# stm32wb55vgy6-breakout.net
KiCad netlist of a schematic drawn in EAGLE
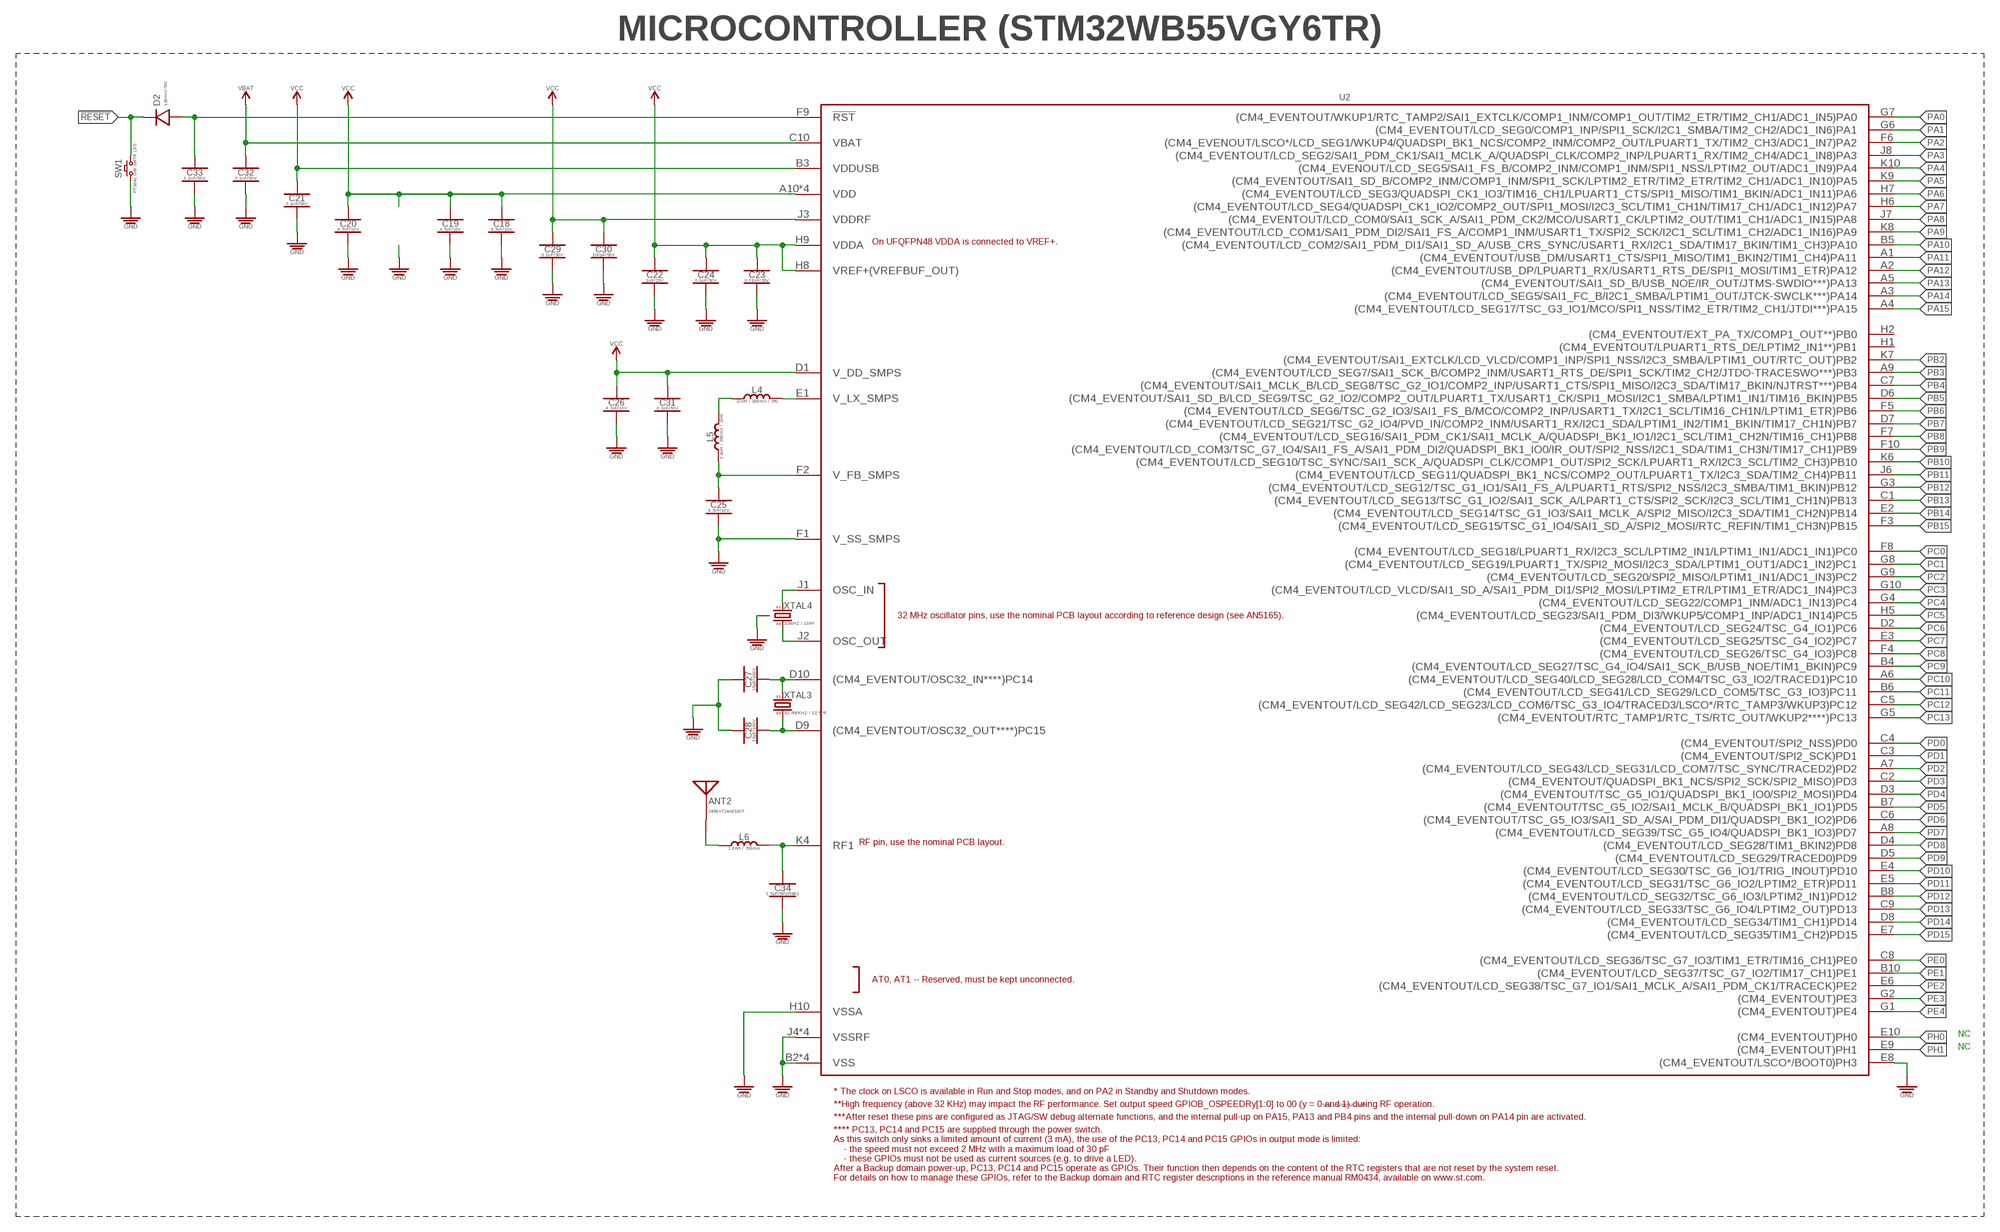
[diagram p0: schematic, sheet 1, part 1 of 2]
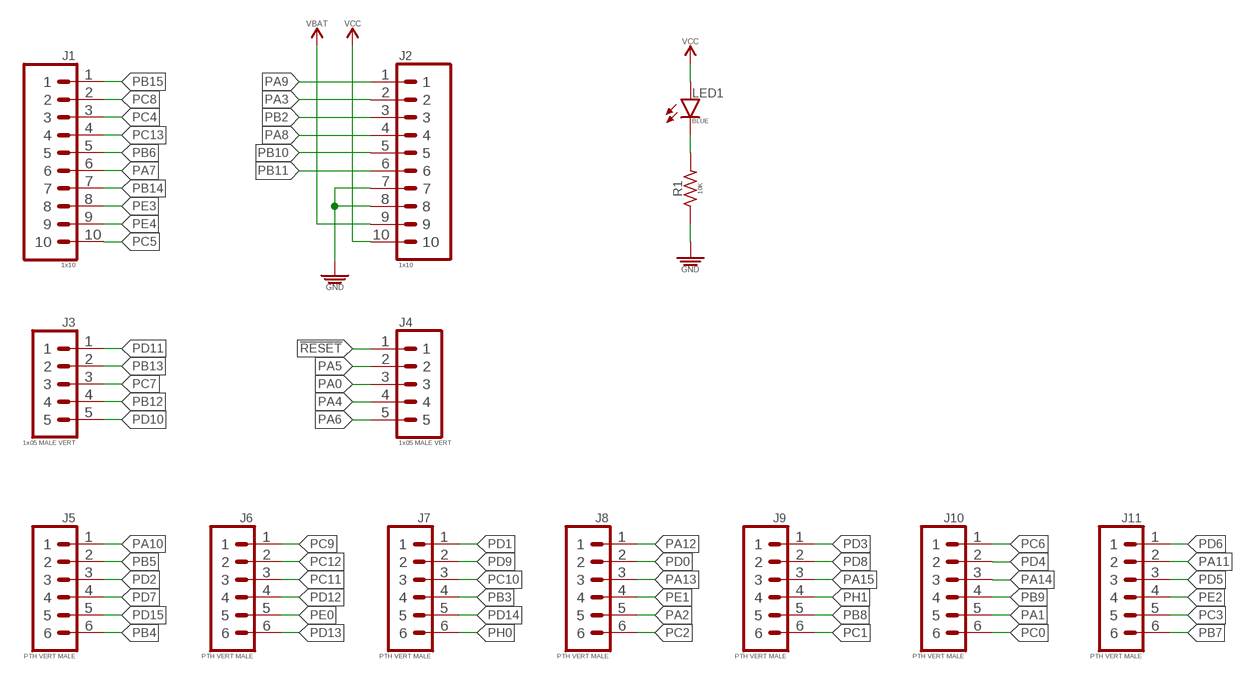
[diagram p1: schematic, sheet 1, part 2 of 2]

(export (version "E")
  (design (tool "Eeschema 10.0.6"))
  (components
    (comp (ref "ANT2")
      (value "2450AT14A0100T")
      (footprint "eagle-import:RESC1608X40N")
      (fields (field (name "MFR") "Johanson Technology Inc."))
      (libsource (lib "eagle-import") (part "2.4GHZ-1PIN"))
    )
    (comp (ref "C18")
      (value "4.7uF/10V")
      (footprint "eagle-import:CAPC1005X55_SMD-0402")
      (fields (field (name "MFR") "Samsung Electro-Mechanics") (field (name "MPN") "CL05A475MP5NRNC"))
      (libsource (lib "eagle-import") (part "4.7UF_CER_SMD-0402_10V-20%"))
    )
    (comp (ref "C19")
      (value "4.7uF/10V")
      (footprint "eagle-import:CAPC1005X55_SMD-0402")
      (fields (field (name "MFR") "Samsung Electro-Mechanics") (field (name "MPN") "CL05A475MP5NRNC"))
      (libsource (lib "eagle-import") (part "4.7UF_CER_SMD-0402_10V-20%"))
    )
    (comp (ref "C20")
      (value "4.7uF/10V")
      (footprint "eagle-import:CAPC1005X55_SMD-0402")
      (fields (field (name "MFR") "Samsung Electro-Mechanics") (field (name "MPN") "CL05A475MP5NRNC"))
      (libsource (lib "eagle-import") (part "4.7UF_CER_SMD-0402_10V-20%"))
    )
    (comp (ref "C21")
      (value "0.1uF/50V")
      (footprint "eagle-import:CAPC1005X55_SMD-0402")
      (fields (field (name "MFR") "TDK Corporation") (field (name "MPN") "C1005X7R1H104K050BE"))
      (libsource (lib "eagle-import") (part "0.1UF_SMD-0402_50V-10%"))
    )
    (comp (ref "C22")
      (value "1uF/25V")
      (footprint "eagle-import:CAPC1005X55_SMD-0402")
      (fields (field (name "MFR") "TDK Corporation") (field (name "MPN") "CGB2A1X5R1E105K033BC"))
      (libsource (lib "eagle-import") (part "1UF_CER_SMD-0402_25V-10%"))
    )
    (comp (ref "C23")
      (value "0.01uF/35V")
      (footprint "eagle-import:CAPC1005X55_SMD-0402")
      (fields (field (name "MFR") "TDK Corporation") (field (name "MPN") "CGA2B3X5R1V103K050BB"))
      (libsource (lib "eagle-import") (part "0.01UF_CER_SMD-0402_35V-10%"))
    )
    (comp (ref "C24")
      (value "0.1uF/50V")
      (footprint "eagle-import:CAPC1005X55_SMD-0402")
      (fields (field (name "MFR") "TDK Corporation") (field (name "MPN") "C1005X7R1H104K050BE"))
      (libsource (lib "eagle-import") (part "0.1UF_SMD-0402_50V-10%"))
    )
    (comp (ref "C25")
      (value "4.7uF/10V")
      (footprint "eagle-import:CAPC1005X55_SMD-0402")
      (fields (field (name "MFR") "Samsung Electro-Mechanics") (field (name "MPN") "CL05A475MP5NRNC"))
      (libsource (lib "eagle-import") (part "4.7UF_CER_SMD-0402_10V-20%"))
    )
    (comp (ref "C26")
      (value "4.7uF/10V")
      (footprint "eagle-import:CAPC1005X55_SMD-0402")
      (fields (field (name "MFR") "Samsung Electro-Mechanics") (field (name "MPN") "CL05A475MP5NRNC"))
      (libsource (lib "eagle-import") (part "4.7UF_CER_SMD-0402_10V-20%"))
    )
    (comp (ref "C27")
      (value "15pF/100V")
      (footprint "eagle-import:CAPC1005X55_SMD-0402")
      (fields (field (name "MFR") "Taiyo Yuden") (field (name "MPN") "HMK105CG150JV-F"))
      (libsource (lib "eagle-import") (part "15PF_SMD-0402_100V-10%"))
    )
    (comp (ref "C28")
      (value "15pF/100V")
      (footprint "eagle-import:CAPC1005X55_SMD-0402")
      (fields (field (name "MFR") "Taiyo Yuden") (field (name "MPN") "HMK105CG150JV-F"))
      (libsource (lib "eagle-import") (part "15PF_SMD-0402_100V-10%"))
    )
    (comp (ref "C29")
      (value "0.1uF/50V")
      (footprint "eagle-import:CAPC1005X55_SMD-0402")
      (fields (field (name "MFR") "TDK Corporation") (field (name "MPN") "C1005X7R1H104K050BE"))
      (libsource (lib "eagle-import") (part "0.1UF_SMD-0402_50V-10%"))
    )
    (comp (ref "C30")
      (value "100pF/50V")
      (footprint "eagle-import:CAPC1005X55_SMD-0402")
      (fields (field (name "MFR") "AVX Corporation") (field (name "MPN") "04025C101KAT2A"))
      (libsource (lib "eagle-import") (part "100PF_SMD-0402_50V-10%"))
    )
    (comp (ref "C31")
      (value "0.1uF/50V")
      (footprint "eagle-import:CAPC1005X55_SMD-0402")
      (fields (field (name "MFR") "TDK Corporation") (field (name "MPN") "C1005X7R1H104K050BE"))
      (libsource (lib "eagle-import") (part "0.1UF_SMD-0402_50V-10%"))
    )
    (comp (ref "C32")
      (value "0.1uF/50V")
      (footprint "eagle-import:CAPC1005X55_SMD-0402")
      (fields (field (name "MFR") "TDK Corporation") (field (name "MPN") "C1005X7R1H104K050BE"))
      (libsource (lib "eagle-import") (part "0.1UF_SMD-0402_50V-10%"))
    )
    (comp (ref "C33")
      (value "0.1uF/50V")
      (footprint "eagle-import:CAPC1005X55_SMD-0402")
      (fields (field (name "MFR") "TDK Corporation") (field (name "MPN") "C1005X7R1H104K050BE"))
      (libsource (lib "eagle-import") (part "0.1UF_SMD-0402_50V-10%"))
    )
    (comp (ref "C34")
      (value "1.5pF/50V/0402")
      (footprint "eagle-import:CAPC1005X55_SMD-0402")
      (fields (field (name "MFR") "Taiyo Yuden") (field (name "MPN") "UVK105CH1R5BW-F"))
      (libsource (lib "eagle-import") (part "1.5PF_CER_SMD-0402-100V-5%"))
    )
    (comp (ref "D2")
      (value "150mA/75V")
      (footprint "eagle-import:DFN100X60X55-2")
      (fields (field (name "MFR") "Comchip Technology") (field (name "MPN") "CDSQR4148-HF"))
      (libsource (lib "eagle-import") (part "GENERAL-PURPOSE_SMD-0402_GP_150MA-75V"))
    )
    (comp (ref "J1")
      (value "1x10")
      (footprint "eagle-import:HDRV10W64P254_1X10_2540X254X838B")
      (fields (field (name "MFR") "Sullins Connector Solutions") (field (name "MPN") "PEC10SAAN"))
      (libsource (lib "eagle-import") (part "1X10_PTH_VERT-MALE_2.54MM"))
    )
    (comp (ref "J2")
      (value "1x10")
      (footprint "eagle-import:HDRV10W64P254_1X10_2540X254X838B")
      (fields (field (name "MFR") "Sullins Connector Solutions") (field (name "MPN") "PEC10SAAN"))
      (libsource (lib "eagle-import") (part "1X10_PTH_VERT-MALE_2.54MM"))
    )
    (comp (ref "J3")
      (value "1x05 MALE VERT")
      (footprint "eagle-import:HDRV5W64P254_1X5_1270X254X838B")
      (fields (field (name "MFR") "Sullins Connector Solutions") (field (name "MPN") "PEC05SAAN"))
      (libsource (lib "eagle-import") (part "1X05_PTH_VERT_MALE_2.54MM"))
    )
    (comp (ref "J4")
      (value "1x05 MALE VERT")
      (footprint "eagle-import:HDRV5W64P254_1X5_1270X254X838B")
      (fields (field (name "MFR") "Sullins Connector Solutions") (field (name "MPN") "PEC05SAAN"))
      (libsource (lib "eagle-import") (part "1X05_PTH_VERT_MALE_2.54MM"))
    )
    (comp (ref "J5")
      (value "PTH VERT MALE")
      (footprint "eagle-import:HDRV6W64P254_1X6_1524X254X838B")
      (fields (field (name "MFR") "Sullins Connector Solutions") (field (name "MPN") "PEC06SAAN"))
      (libsource (lib "eagle-import") (part "1X06_PTH_VERT_MALE_2.54MM"))
    )
    (comp (ref "J6")
      (value "PTH VERT MALE")
      (footprint "eagle-import:HDRV6W64P254_1X6_1524X254X838B")
      (fields (field (name "MFR") "Sullins Connector Solutions") (field (name "MPN") "PEC06SAAN"))
      (libsource (lib "eagle-import") (part "1X06_PTH_VERT_MALE_2.54MM"))
    )
    (comp (ref "J7")
      (value "PTH VERT MALE")
      (footprint "eagle-import:HDRV6W64P254_1X6_1524X254X838B")
      (fields (field (name "MFR") "Sullins Connector Solutions") (field (name "MPN") "PEC06SAAN"))
      (libsource (lib "eagle-import") (part "1X06_PTH_VERT_MALE_2.54MM"))
    )
    (comp (ref "J8")
      (value "PTH VERT MALE")
      (footprint "eagle-import:HDRV6W64P254_1X6_1524X254X838B")
      (fields (field (name "MFR") "Sullins Connector Solutions") (field (name "MPN") "PEC06SAAN"))
      (libsource (lib "eagle-import") (part "1X06_PTH_VERT_MALE_2.54MM"))
    )
    (comp (ref "J9")
      (value "PTH VERT MALE")
      (footprint "eagle-import:HDRV6W64P254_1X6_1524X254X838B")
      (fields (field (name "MFR") "Sullins Connector Solutions") (field (name "MPN") "PEC06SAAN"))
      (libsource (lib "eagle-import") (part "1X06_PTH_VERT_MALE_2.54MM"))
    )
    (comp (ref "J10")
      (value "PTH VERT MALE")
      (footprint "eagle-import:HDRV6W64P254_1X6_1524X254X838B")
      (fields (field (name "MFR") "Sullins Connector Solutions") (field (name "MPN") "PEC06SAAN"))
      (libsource (lib "eagle-import") (part "1X06_PTH_VERT_MALE_2.54MM"))
    )
    (comp (ref "J11")
      (value "PTH VERT MALE")
      (footprint "eagle-import:HDRV6W64P254_1X6_1524X254X838B")
      (fields (field (name "MFR") "Sullins Connector Solutions") (field (name "MPN") "PEC06SAAN"))
      (libsource (lib "eagle-import") (part "1X06_PTH_VERT_MALE_2.54MM"))
    )
    (comp (ref "L4")
      (value "10nH / 200mA / 2%")
      (footprint "eagle-import:INDC1005X32N")
      (fields (field (name "MFR") "TE Connectivity Passive Product") (field (name "MPN") "36401E10NGTDF"))
      (libsource (lib "eagle-import") (part "10NH_SMD-0402_200MA-1.35OHM-2%"))
    )
    (comp (ref "L5")
      (value "2.2uH / 350mA / 20%")
      (footprint "eagle-import:INDC1005X32N")
      (fields (field (name "MFR") "TDK Corporation") (field (name "MPN") "MLZ1005M2R2WT000"))
      (libsource (lib "eagle-import") (part "2.2UH_SMD-0402_350MA-0.550OHM-20%"))
    )
    (comp (ref "L6")
      (value "1.8nH / 700mA")
      (footprint "eagle-import:INDC1005X32N")
      (fields (field (name "MFR") "Taiyo Yuden") (field (name "MPN") "HK10051N8S-T"))
      (libsource (lib "eagle-import") (part "1.8NH_SMD-0402_200MA-1.35OHM-2%"))
    )
    (comp (ref "LED1")
      (value "BLUE")
      (footprint "eagle-import:LEDC1005X40_LED-0402")
      (fields (field (name "MFR") "Bivar Inc.") (field (name "MPN") "SM0402BWC"))
      (libsource (lib "eagle-import") (part "LED_SMD-0402_DISCRETE_BLUE"))
    )
    (comp (ref "R1")
      (value "10K")
      (footprint "eagle-import:RESC1005X35_SMD-0402")
      (fields (field (name "MFR") "Yageo") (field (name "MPN") "RC0402JR-0710KP"))
      (libsource (lib "eagle-import") (part "10KΩ_SMD-0402_1/16W-5%"))
    )
    (comp (ref "SW1")
      (value "PTS841 GM SMTR LFS")
      (footprint "eagle-import:SW_MOMENTARY_SPST-NO_PTS841-GM-SMTR-LFS")
      (fields (field (name "MFR") "C&K"))
      (libsource (lib "eagle-import") (part "SWITCH_MOMENTARY_PTS841GMSMTRLFS"))
    )
    (comp (ref "U2")
      (value "STM32WB55VGY6TR")
      (footprint "eagle-import:BGA100N40P10X10_438X440X59N")
      (fields (field (name "MFR") "STMicroelectronics"))
      (libsource (lib "eagle-import") (part "STM32WB55VXYX-STM32WB55VGY6"))
    )
    (comp (ref "XTAL3")
      (value "32.768KHZ / 12.5PF")
      (footprint "eagle-import:OSCCC205X120X55N")
      (fields (field (name "MFR") "NDK America, Inc.") (field (name "MPN") "NX2012SA-32.768K-STD-MUB-1"))
      (libsource (lib "eagle-import") (part "CRYSTAL-2_NX2012SA_23K768_12.5PF"))
    )
    (comp (ref "XTAL4")
      (value "32MHZ / 10PF")
      (footprint "eagle-import:OSCCC200X160X59N")
      (fields (field (name "MFR") "Abracon LLC") (field (name "MPN") "ABM11-32.000MHZ-D2X-T3"))
      (libsource (lib "eagle-import") (part "CRYSTAL-4_ABM11_32MHZ_10PF"))
    )
  )
  (nets
    (net (code "1") (name "/~{RESET}") (class "Default")
      (node (ref "D2") (pin "K") (pinfunction "K_K") (pintype "passive"))
      (node (ref "J4") (pin "1") (pinfunction "1_1") (pintype "passive"))
      (node (ref "SW1") (pin "3") (pinfunction "2_3") (pintype "passive"))
      (node (ref "SW1") (pin "4") (pinfunction "2_4") (pintype "passive"))
    )
    (net (code "2") (name "GND") (class "Default")
      (node (ref "C18") (pin "2") (pinfunction "2_2") (pintype "passive"))
      (node (ref "C19") (pin "2") (pinfunction "2_2") (pintype "passive"))
      (node (ref "C20") (pin "2") (pinfunction "2_2") (pintype "passive"))
      (node (ref "C21") (pin "2") (pinfunction "2_2") (pintype "passive"))
      (node (ref "C22") (pin "2") (pinfunction "2_2") (pintype "passive"))
      (node (ref "C23") (pin "2") (pinfunction "2_2") (pintype "passive"))
      (node (ref "C24") (pin "2") (pinfunction "2_2") (pintype "passive"))
      (node (ref "C25") (pin "2") (pinfunction "2_2") (pintype "passive"))
      (node (ref "C26") (pin "2") (pinfunction "2_2") (pintype "passive"))
      (node (ref "C27") (pin "1") (pinfunction "1_1") (pintype "passive"))
      (node (ref "C28") (pin "1") (pinfunction "1_1") (pintype "passive"))
      (node (ref "C29") (pin "2") (pinfunction "2_2") (pintype "passive"))
      (node (ref "C30") (pin "2") (pinfunction "2_2") (pintype "passive"))
      (node (ref "C31") (pin "2") (pinfunction "2_2") (pintype "passive"))
      (node (ref "C32") (pin "2") (pinfunction "2_2") (pintype "passive"))
      (node (ref "C33") (pin "2") (pinfunction "2_2") (pintype "passive"))
      (node (ref "C34") (pin "2") (pinfunction "2_2") (pintype "passive"))
      (node (ref "J2") (pin "7") (pinfunction "7_7") (pintype "passive"))
      (node (ref "J2") (pin "8") (pinfunction "8_8") (pintype "passive"))
      (node (ref "R1") (pin "1") (pinfunction "1_1") (pintype "passive"))
      (node (ref "SW1") (pin "1") (pinfunction "1_1") (pintype "passive"))
      (node (ref "SW1") (pin "2") (pinfunction "1_2") (pintype "passive"))
      (node (ref "U2") (pin "B2") (pinfunction "VSS_B2") (pintype "power_in"))
      (node (ref "U2") (pin "B9") (pinfunction "VSS_B9") (pintype "power_in"))
      (node (ref "U2") (pin "E8") (pinfunction "(CM4_EVENTOUT/LSCO*/BOOT0)PH3_E8") (pintype "bidirectional"))
      (node (ref "U2") (pin "F1") (pinfunction "V_SS_SMPS_F1") (pintype "power_in"))
      (node (ref "U2") (pin "H10") (pinfunction "VSSA_H10") (pintype "power_in"))
      (node (ref "U2") (pin "J4") (pinfunction "VSSRF_J4") (pintype "power_in"))
      (node (ref "U2") (pin "J5") (pinfunction "VSS_J5") (pintype "power_in"))
      (node (ref "U2") (pin "J9") (pinfunction "VSS_J9") (pintype "power_in"))
      (node (ref "U2") (pin "K1") (pinfunction "VSSRF_K1") (pintype "power_in"))
      (node (ref "U2") (pin "K2") (pinfunction "VSSRF_K2") (pintype "power_in"))
      (node (ref "U2") (pin "K3") (pinfunction "VSSRF_K3") (pintype "power_in"))
      (node (ref "XTAL4") (pin "2") (pinfunction "GND_2") (pintype "passive"))
      (node (ref "XTAL4") (pin "4") (pinfunction "GND_4") (pintype "passive"))
    )
    (net (code "3") (name "Net-(ANT2-PadFEED)") (class "Default")
      (node (ref "ANT2") (pin "FEED") (pinfunction "FEED_FEED") (pintype "passive"))
      (node (ref "L6") (pin "1") (pinfunction "1_1") (pintype "passive"))
    )
    (net (code "4") (name "Net-(L4-Pad1)") (class "Default")
      (node (ref "L4") (pin "1") (pinfunction "1_1") (pintype "passive"))
      (node (ref "L5") (pin "2") (pinfunction "2_2") (pintype "passive"))
    )
    (net (code "5") (name "Net-(LED1-PadK)") (class "Default")
      (node (ref "LED1") (pin "K") (pinfunction "K_K") (pintype "passive"))
      (node (ref "R1") (pin "2") (pinfunction "2_2") (pintype "passive"))
    )
    (net (code "6") (name "Net-(U2-(CM4_EVENTOUT{slash}OSC32_IN****)PC14)") (class "Default")
      (node (ref "C27") (pin "2") (pinfunction "2_2") (pintype "passive"))
      (node (ref "U2") (pin "D10") (pinfunction "(CM4_EVENTOUT/OSC32_IN****)PC14_D10") (pintype "bidirectional"))
      (node (ref "XTAL3") (pin "X1") (pinfunction "X1_X1") (pintype "passive"))
    )
    (net (code "7") (name "Net-(U2-(CM4_EVENTOUT{slash}OSC32_OUT****)PC15)") (class "Default")
      (node (ref "C28") (pin "2") (pinfunction "2_2") (pintype "passive"))
      (node (ref "U2") (pin "D9") (pinfunction "(CM4_EVENTOUT/OSC32_OUT****)PC15_D9") (pintype "bidirectional"))
      (node (ref "XTAL3") (pin "X2") (pinfunction "X2_X2") (pintype "passive"))
    )
    (net (code "8") (name "Net-(U2-OSC_IN)") (class "Default")
      (node (ref "U2") (pin "J1") (pinfunction "OSC_IN_J1") (pintype "bidirectional"))
      (node (ref "XTAL4") (pin "1") (pinfunction "XTAL1_1") (pintype "passive"))
    )
    (net (code "9") (name "Net-(U2-OSC_OUT)") (class "Default")
      (node (ref "U2") (pin "J2") (pinfunction "OSC_OUT_J2") (pintype "bidirectional"))
      (node (ref "XTAL4") (pin "3") (pinfunction "XTAL2_3") (pintype "passive"))
    )
    (net (code "10") (name "Net-(U2-RF1)") (class "Default")
      (node (ref "C34") (pin "1") (pinfunction "1_1") (pintype "passive"))
      (node (ref "L6") (pin "2") (pinfunction "2_2") (pintype "passive"))
      (node (ref "U2") (pin "K4") (pinfunction "RF1_K4") (pintype "bidirectional"))
    )
    (net (code "11") (name "Net-(U2-V_FB_SMPS)") (class "Default")
      (node (ref "C25") (pin "1") (pinfunction "1_1") (pintype "passive"))
      (node (ref "L5") (pin "1") (pinfunction "1_1") (pintype "passive"))
      (node (ref "U2") (pin "F2") (pinfunction "V_FB_SMPS_F2") (pintype "power_in"))
    )
    (net (code "12") (name "Net-(U2-V_LX_SMPS)") (class "Default")
      (node (ref "L4") (pin "2") (pinfunction "2_2") (pintype "passive"))
      (node (ref "U2") (pin "E1") (pinfunction "V_LX_SMPS_E1") (pintype "power_in"))
    )
    (net (code "13") (name "Net-(U2-~{RST})") (class "Default")
      (node (ref "C33") (pin "1") (pinfunction "1_1") (pintype "passive"))
      (node (ref "D2") (pin "A") (pinfunction "A_A") (pintype "passive"))
      (node (ref "U2") (pin "F9") (pinfunction "~{RST}_F9") (pintype "bidirectional"))
    )
    (net (code "14") (name "PA0") (class "Default")
      (node (ref "J4") (pin "3") (pinfunction "3_3") (pintype "passive"))
      (node (ref "U2") (pin "G7") (pinfunction "(CM4_EVENTOUT/WKUP1/RTC_TAMP2/SAI1_EXTCLK/COMP1_INM/COMP1_OUT/TIM2_ETR/TIM2_CH1/ADC1_IN5)PA0_G7") (pintype "bidirectional"))
    )
    (net (code "15") (name "PA1") (class "Default")
      (node (ref "J10") (pin "5") (pinfunction "5_5") (pintype "passive"))
      (node (ref "U2") (pin "G6") (pinfunction "(CM4_EVENTOUT/LCD_SEG0/COMP1_INP/SPI1_SCK/I2C1_SMBA/TIM2_CH2/ADC1_IN6)PA1_G6") (pintype "bidirectional"))
    )
    (net (code "16") (name "PA2") (class "Default")
      (node (ref "J8") (pin "5") (pinfunction "5_5") (pintype "passive"))
      (node (ref "U2") (pin "F6") (pinfunction "(CM4_EVENOUT/LSCO*/LCD_SEG1/WKUP4/QUADSPI_BK1_NCS/COMP2_INM/COMP2_OUT/LPUART1_TX/TIM2_CH3/ADC1_IN7)PA2_F6") (pintype "bidirectional"))
    )
    (net (code "17") (name "PA3") (class "Default")
      (node (ref "J2") (pin "2") (pinfunction "2_2") (pintype "passive"))
      (node (ref "U2") (pin "J8") (pinfunction "(CM4_EVENTOUT/LCD_SEG2/SAI1_PDM_CK1/SAI1_MCLK_A/QUADSPI_CLK/COMP2_INP/LPUART1_RX/TIM2_CH4/ADC1_IN8)PA3_J8") (pintype "bidirectional"))
    )
    (net (code "18") (name "PA4") (class "Default")
      (node (ref "J4") (pin "4") (pinfunction "4_4") (pintype "passive"))
      (node (ref "U2") (pin "K10") (pinfunction "(CM4_EVENOUT/LCD_SEG5/SAI1_FS_B/COMP2_INM/COMP1_INM/SPI1_NSS/LPTIM2_OUT/ADC1_IN9)PA4_K10") (pintype "bidirectional"))
    )
    (net (code "19") (name "PA5") (class "Default")
      (node (ref "J4") (pin "2") (pinfunction "2_2") (pintype "passive"))
      (node (ref "U2") (pin "K9") (pinfunction "(CM4_EVENTOUT/SAI1_SD_B/COMP2_INM/COMP1_INM/SPI1_SCK/LPTIM2_ETR/TIM2_ETR/TIM2_CH1/ADC1_IN10)PA5_K9") (pintype "bidirectional"))
    )
    (net (code "20") (name "PA6") (class "Default")
      (node (ref "J4") (pin "5") (pinfunction "5_5") (pintype "passive"))
      (node (ref "U2") (pin "H7") (pinfunction "(CM4_EVENTOUT/LCD_SEG3/QUADSPI_CK1_IO3/TIM16_CH1/LPUART1_CTS/SPI1_MISO/TIM1_BKIN/ADC1_IN11)PA6_H7") (pintype "bidirectional"))
    )
    (net (code "21") (name "PA7") (class "Default")
      (node (ref "J1") (pin "6") (pinfunction "6_6") (pintype "passive"))
      (node (ref "U2") (pin "H6") (pinfunction "(CM4_EVENTOUT/LCD_SEG4/QUADSPI_CK1_IO2/COMP2_OUT/SPI1_MOSI/I2C3_SCL/TIM1_CH1N/TIM17_CH1/ADC1_IN12)PA7_H6") (pintype "bidirectional"))
    )
    (net (code "22") (name "PA8") (class "Default")
      (node (ref "J2") (pin "4") (pinfunction "4_4") (pintype "passive"))
      (node (ref "U2") (pin "J7") (pinfunction "(CM4_EVENTOUT/LCD_COM0/SAI1_SCK_A/SAI1_PDM_CK2/MCO/USART1_CK/LPTIM2_OUT/TIM1_CH1/ADC1_IN15)PA8_J7") (pintype "bidirectional"))
    )
    (net (code "23") (name "PA9") (class "Default")
      (node (ref "J2") (pin "1") (pinfunction "1_1") (pintype "passive"))
      (node (ref "U2") (pin "K8") (pinfunction "(CM4_EVENTOUT/LCD_COM1/SAI1_PDM_DI2/SAI1_FS_A/COMP1_INM/USART1_TX/SPI2_SCK/I2C1_SCL/TIM1_CH2/ADC1_IN16)PA9_K8") (pintype "bidirectional"))
    )
    (net (code "24") (name "PA10") (class "Default")
      (node (ref "J5") (pin "1") (pinfunction "1_1") (pintype "passive"))
      (node (ref "U2") (pin "B5") (pinfunction "(CM4_EVENTOUT/LCD_COM2/SAI1_PDM_DI1/SAI1_SD_A/USB_CRS_SYNC/USART1_RX/I2C1_SDA/TIM17_BKIN/TIM1_CH3)PA10_B5") (pintype "bidirectional"))
    )
    (net (code "25") (name "PA11") (class "Default")
      (node (ref "J11") (pin "2") (pinfunction "2_2") (pintype "passive"))
      (node (ref "U2") (pin "A1") (pinfunction "(CM4_EVENTOUT/USB_DM/USART1_CTS/SPI1_MISO/TIM1_BKIN2/TIM1_CH4)PA11_A1") (pintype "bidirectional"))
    )
    (net (code "26") (name "PA12") (class "Default")
      (node (ref "J8") (pin "1") (pinfunction "1_1") (pintype "passive"))
      (node (ref "U2") (pin "A2") (pinfunction "(CM4_EVENTOUT/USB_DP/LPUART1_RX/USART1_RTS_DE/SPI1_MOSI/TIM1_ETR)PA12_A2") (pintype "bidirectional"))
    )
    (net (code "27") (name "PA13") (class "Default")
      (node (ref "J8") (pin "3") (pinfunction "3_3") (pintype "passive"))
      (node (ref "U2") (pin "A5") (pinfunction "(CM4_EVENTOUT/SAI1_SD_B/USB_NOE/IR_OUT/JTMS-SWDIO***)PA13_A5") (pintype "bidirectional"))
    )
    (net (code "28") (name "PA14") (class "Default")
      (node (ref "J10") (pin "3") (pinfunction "3_3") (pintype "passive"))
      (node (ref "U2") (pin "A3") (pinfunction "(CM4_EVENTOUT/LCD_SEG5/SAI1_FC_B/I2C1_SMBA/LPTIM1_OUT/JTCK-SWCLK***)PA14_A3") (pintype "bidirectional"))
    )
    (net (code "29") (name "PA15") (class "Default")
      (node (ref "J9") (pin "3") (pinfunction "3_3") (pintype "passive"))
      (node (ref "U2") (pin "A4") (pinfunction "(CM4_EVENTOUT/LCD_SEG17/TSC_G3_IO1/MCO/SPI1_NSS/TIM2_ETR/TIM2_CH1/JTDI***)PA15_A4") (pintype "bidirectional"))
    )
    (net (code "30") (name "PB2") (class "Default")
      (node (ref "J2") (pin "3") (pinfunction "3_3") (pintype "passive"))
      (node (ref "U2") (pin "K7") (pinfunction "(CM4_EVENTOUT/SAI1_EXTCLK/LCD_VLCD/COMP1_INP/SPI1_NSS/I2C3_SMBA/LPTIM1_OUT/RTC_OUT)PB2_K7") (pintype "bidirectional"))
    )
    (net (code "31") (name "PB3") (class "Default")
      (node (ref "J7") (pin "4") (pinfunction "4_4") (pintype "passive"))
      (node (ref "U2") (pin "A9") (pinfunction "(CM4_EVENTOUT/LCD_SEG7/SAI1_SCK_B/COMP2_INM/USART1_RTS_DE/SPI1_SCK/TIM2_CH2/JTDO-TRACESWO***)PB3_A9") (pintype "bidirectional"))
    )
    (net (code "32") (name "PB4") (class "Default")
      (node (ref "J5") (pin "6") (pinfunction "6_6") (pintype "passive"))
      (node (ref "U2") (pin "C7") (pinfunction "(CM4_EVENTOUT/SAI1_MCLK_B/LCD_SEG8/TSC_G2_IO1/COMP2_INP/USART1_CTS/SPI1_MISO/I2C3_SDA/TIM17_BKIN/NJTRST***)PB4_C7") (pintype "bidirectional"))
    )
    (net (code "33") (name "PB5") (class "Default")
      (node (ref "J5") (pin "2") (pinfunction "2_2") (pintype "passive"))
      (node (ref "U2") (pin "D6") (pinfunction "(CM4_EVENTOUT/SAI1_SD_B/LCD_SEG9/TSC_G2_IO2/COMP2_OUT/LPUART1_TX/USART1_CK/SPI1_MOSI/I2C1_SMBA/LPTIM1_IN1/TIM16_BKIN)PB5_D6") (pintype "bidirectional"))
    )
    (net (code "34") (name "PB6") (class "Default")
      (node (ref "J1") (pin "5") (pinfunction "5_5") (pintype "passive"))
      (node (ref "U2") (pin "F5") (pinfunction "(CM4_EVENTOUT/LCD_SEG6/TSC_G2_IO3/SAI1_FS_B/MCO/COMP2_INP/USART1_TX/I2C1_SCL/TIM16_CH1N/LPTIM1_ETR)PB6_F5") (pintype "bidirectional"))
    )
    (net (code "35") (name "PB7") (class "Default")
      (node (ref "J11") (pin "6") (pinfunction "6_6") (pintype "passive"))
      (node (ref "U2") (pin "D7") (pinfunction "(CM4_EVENTOUT/LCD_SEG21/TSC_G2_IO4/PVD_IN/COMP2_INM/USART1_RX/I2C1_SDA/LPTIM1_IN2/TIM1_BKIN/TIM17_CH1N)PB7_D7") (pintype "bidirectional"))
    )
    (net (code "36") (name "PB8") (class "Default")
      (node (ref "J9") (pin "5") (pinfunction "5_5") (pintype "passive"))
      (node (ref "U2") (pin "F7") (pinfunction "(CM4_EVENTOUT/LCD_SEG16/SAI1_PDM_CK1/SAI1_MCLK_A/QUADSPI_BK1_IO1/I2C1_SCL/TIM1_CH2N/TIM16_CH1)PB8_F7") (pintype "bidirectional"))
    )
    (net (code "37") (name "PB9") (class "Default")
      (node (ref "J10") (pin "4") (pinfunction "4_4") (pintype "passive"))
      (node (ref "U2") (pin "F10") (pinfunction "(CM4_EVENTOUT/LCD_COM3/TSC_G7_IO4/SAI1_FS_A/SAI1_PDM_DI2/QUADSPI_BK1_IO0/IR_OUT/SPI2_NSS/I2C1_SDA/TIM1_CH3N/TIM17_CH1)PB9_F10") (pintype "bidirectional"))
    )
    (net (code "38") (name "PB10") (class "Default")
      (node (ref "J2") (pin "5") (pinfunction "5_5") (pintype "passive"))
      (node (ref "U2") (pin "K6") (pinfunction "(CM4_EVENTOUT/LCD_SEG10/TSC_SYNC/SAI1_SCK_A/QUADSPI_CLK/COMP1_OUT/SPI2_SCK/LPUART1_RX/I2C3_SCL/TIM2_CH3)PB10_K6") (pintype "bidirectional"))
    )
    (net (code "39") (name "PB11") (class "Default")
      (node (ref "J2") (pin "6") (pinfunction "6_6") (pintype "passive"))
      (node (ref "U2") (pin "J6") (pinfunction "(CM4_EVENTOUT/LCD_SEG11/QUADSPI_BK1_NCS/COMP2_OUT/LPUART1_TX/I2C3_SDA/TIM2_CH4)PB11_J6") (pintype "bidirectional"))
    )
    (net (code "40") (name "PB12") (class "Default")
      (node (ref "J3") (pin "4") (pinfunction "4_4") (pintype "passive"))
      (node (ref "U2") (pin "G3") (pinfunction "(CM4_EVENTOUT/LCD_SEG12/TSC_G1_IO1/SAI1_FS_A/LPUART1_RTS/SPI2_NSS/I2C3_SMBA/TIM1_BKIN)PB12_G3") (pintype "bidirectional"))
    )
    (net (code "41") (name "PB13") (class "Default")
      (node (ref "J3") (pin "2") (pinfunction "2_2") (pintype "passive"))
      (node (ref "U2") (pin "C1") (pinfunction "(CM4_EVENTOUT/LCD_SEG13/TSC_G1_IO2/SAI1_SCK_A/LPART1_CTS/SPI2_SCK/I2C3_SCL/TIM1_CH1N)PB13_C1") (pintype "bidirectional"))
    )
    (net (code "42") (name "PB14") (class "Default")
      (node (ref "J1") (pin "7") (pinfunction "7_7") (pintype "passive"))
      (node (ref "U2") (pin "E2") (pinfunction "(CM4_EVENTOUT/LCD_SEG14/TSC_G1_IO3/SAI1_MCLK_A/SPI2_MISO/I2C3_SDA/TIM1_CH2N)PB14_E2") (pintype "bidirectional"))
    )
    (net (code "43") (name "PB15") (class "Default")
      (node (ref "J1") (pin "1") (pinfunction "1_1") (pintype "passive"))
      (node (ref "U2") (pin "F3") (pinfunction "(CM4_EVENTOUT/LCD_SEG15/TSC_G1_IO4/SAI1_SD_A/SPI2_MOSI/RTC_REFIN/TIM1_CH3N)PB15_F3") (pintype "bidirectional"))
    )
    (net (code "44") (name "PC0") (class "Default")
      (node (ref "J10") (pin "6") (pinfunction "6_6") (pintype "passive"))
      (node (ref "U2") (pin "F8") (pinfunction "(CM4_EVENTOUT/LCD_SEG18/LPUART1_RX/I2C3_SCL/LPTIM2_IN1/LPTIM1_IN1/ADC1_IN1)PC0_F8") (pintype "bidirectional"))
    )
    (net (code "45") (name "PC1") (class "Default")
      (node (ref "J9") (pin "6") (pinfunction "6_6") (pintype "passive"))
      (node (ref "U2") (pin "G8") (pinfunction "(CM4_EVENTOUT/LCD_SEG19/LPUART1_TX/SPI2_MOSI/I2C3_SDA/LPTIM1_OUT1/ADC1_IN2)PC1_G8") (pintype "bidirectional"))
    )
    (net (code "46") (name "PC2") (class "Default")
      (node (ref "J8") (pin "6") (pinfunction "6_6") (pintype "passive"))
      (node (ref "U2") (pin "G9") (pinfunction "(CM4_EVENTOUT/LCD_SEG20/SPI2_MISO/LPTIM1_IN1/ADC1_IN3)PC2_G9") (pintype "bidirectional"))
    )
    (net (code "47") (name "PC3") (class "Default")
      (node (ref "J11") (pin "5") (pinfunction "5_5") (pintype "passive"))
      (node (ref "U2") (pin "G10") (pinfunction "(CM4_EVENTOUT/LCD_VLCD/SAI1_SD_A/SAI1_PDM_DI1/SPI2_MOSI/LPTIM2_ETR/LPTIM1_ETR/ADC1_IN4)PC3_G10") (pintype "bidirectional"))
    )
    (net (code "48") (name "PC4") (class "Default")
      (node (ref "J1") (pin "3") (pinfunction "3_3") (pintype "passive"))
      (node (ref "U2") (pin "G4") (pinfunction "(CM4_EVENTOUT/LCD_SEG22/COMP1_INM/ADC1_IN13)PC4_G4") (pintype "bidirectional"))
    )
    (net (code "49") (name "PC5") (class "Default")
      (node (ref "J1") (pin "10") (pinfunction "10_10") (pintype "passive"))
      (node (ref "U2") (pin "H5") (pinfunction "(CM4_EVENTOUT/LCD_SEG23/SAI1_PDM_DI3/WKUP5/COMP1_INP/ADC1_IN14)PC5_H5") (pintype "bidirectional"))
    )
    (net (code "50") (name "PC6") (class "Default")
      (node (ref "J10") (pin "1") (pinfunction "1_1") (pintype "passive"))
      (node (ref "U2") (pin "D2") (pinfunction "(CM4_EVENTOUT/LCD_SEG24/TSC_G4_IO1)PC6_D2") (pintype "bidirectional"))
    )
    (net (code "51") (name "PC7") (class "Default")
      (node (ref "J3") (pin "3") (pinfunction "3_3") (pintype "passive"))
      (node (ref "U2") (pin "E3") (pinfunction "(CM4_EVENTOUT/LCD_SEG25/TSC_G4_IO2)PC7_E3") (pintype "bidirectional"))
    )
    (net (code "52") (name "PC8") (class "Default")
      (node (ref "J1") (pin "2") (pinfunction "2_2") (pintype "passive"))
      (node (ref "U2") (pin "F4") (pinfunction "(CM4_EVENTOUT/LCD_SEG26/TSC_G4_IO3)PC8_F4") (pintype "bidirectional"))
    )
    (net (code "53") (name "PC9") (class "Default")
      (node (ref "J6") (pin "1") (pinfunction "1_1") (pintype "passive"))
      (node (ref "U2") (pin "B4") (pinfunction "(CM4_EVENTOUT/LCD_SEG27/TSC_G4_IO4/SAI1_SCK_B/USB_NOE/TIM1_BKIN)PC9_B4") (pintype "bidirectional"))
    )
    (net (code "54") (name "PC10") (class "Default")
      (node (ref "J7") (pin "3") (pinfunction "3_3") (pintype "passive"))
      (node (ref "U2") (pin "A6") (pinfunction "(CM4_EVENTOUT/LCD_SEG40/LCD_SEG28/LCD_COM4/TSC_G3_IO2/TRACED1)PC10_A6") (pintype "bidirectional"))
    )
    (net (code "55") (name "PC11") (class "Default")
      (node (ref "J6") (pin "3") (pinfunction "3_3") (pintype "passive"))
      (node (ref "U2") (pin "B6") (pinfunction "(CM4_EVENTOUT/LCD_SEG41/LCD_SEG29/LCD_COM5/TSC_G3_IO3)PC11_B6") (pintype "bidirectional"))
    )
    (net (code "56") (name "PC12") (class "Default")
      (node (ref "J6") (pin "2") (pinfunction "2_2") (pintype "passive"))
      (node (ref "U2") (pin "C5") (pinfunction "(CM4_EVENTOUT/LCD_SEG42/LCD_SEG23/LCD_COM6/TSC_G3_IO4/TRACED3/LSCO*/RTC_TAMP3/WKUP3)PC12_C5") (pintype "bidirectional"))
    )
    (net (code "57") (name "PC13") (class "Default")
      (node (ref "J1") (pin "4") (pinfunction "4_4") (pintype "passive"))
      (node (ref "U2") (pin "G5") (pinfunction "(CM4_EVENTOUT/RTC_TAMP1/RTC_TS/RTC_OUT/WKUP2****)PC13_G5") (pintype "bidirectional"))
    )
    (net (code "58") (name "PD0") (class "Default")
      (node (ref "J8") (pin "2") (pinfunction "2_2") (pintype "passive"))
      (node (ref "U2") (pin "C4") (pinfunction "(CM4_EVENTOUT/SPI2_NSS)PD0_C4") (pintype "bidirectional"))
    )
    (net (code "59") (name "PD1") (class "Default")
      (node (ref "J7") (pin "1") (pinfunction "1_1") (pintype "passive"))
      (node (ref "U2") (pin "C3") (pinfunction "(CM4_EVENTOUT/SPI2_SCK)PD1_C3") (pintype "bidirectional"))
    )
    (net (code "60") (name "PD2") (class "Default")
      (node (ref "J5") (pin "3") (pinfunction "3_3") (pintype "passive"))
      (node (ref "U2") (pin "A7") (pinfunction "(CM4_EVENTOUT/LCD_SEG43/LCD_SEG31/LCD_COM7/TSC_SYNC/TRACED2)PD2_A7") (pintype "bidirectional"))
    )
    (net (code "61") (name "PD3") (class "Default")
      (node (ref "J9") (pin "1") (pinfunction "1_1") (pintype "passive"))
      (node (ref "U2") (pin "C2") (pinfunction "(CM4_EVENTOUT/QUADSPI_BK1_NCS/SPI2_SCK/SPI2_MISO)PD3_C2") (pintype "bidirectional"))
    )
    (net (code "62") (name "PD4") (class "Default")
      (node (ref "J10") (pin "2") (pinfunction "2_2") (pintype "passive"))
      (node (ref "U2") (pin "D3") (pinfunction "(CM4_EVENTOUT/TSC_G5_IO1/QUADSPI_BK1_IO0/SPI2_MOSI)PD4_D3") (pintype "bidirectional"))
    )
    (net (code "63") (name "PD5") (class "Default")
      (node (ref "J11") (pin "3") (pinfunction "3_3") (pintype "passive"))
      (node (ref "U2") (pin "B7") (pinfunction "(CM4_EVENTOUT/TSC_G5_IO2/SAI1_MCLK_B/QUADSPI_BK1_IO1)PD5_B7") (pintype "bidirectional"))
    )
    (net (code "64") (name "PD6") (class "Default")
      (node (ref "J11") (pin "1") (pinfunction "1_1") (pintype "passive"))
      (node (ref "U2") (pin "C6") (pinfunction "(CM4_EVENTOUT/TSC_G5_IO3/SAI1_SD_A/SAI_PDM_DI1/QUADSPI_BK1_IO2)PD6_C6") (pintype "bidirectional"))
    )
    (net (code "65") (name "PD7") (class "Default")
      (node (ref "J5") (pin "4") (pinfunction "4_4") (pintype "passive"))
      (node (ref "U2") (pin "A8") (pinfunction "(CM4_EVENTOUT/LCD_SEG39/TSC_G5_IO4/QUADSPI_BK1_IO3)PD7_A8") (pintype "bidirectional"))
    )
    (net (code "66") (name "PD8") (class "Default")
      (node (ref "J9") (pin "2") (pinfunction "2_2") (pintype "passive"))
      (node (ref "U2") (pin "D4") (pinfunction "(CM4_EVENTOUT/LCD_SEG28/TIM1_BKIN2)PD8_D4") (pintype "bidirectional"))
    )
    (net (code "67") (name "PD9") (class "Default")
      (node (ref "J7") (pin "2") (pinfunction "2_2") (pintype "passive"))
      (node (ref "U2") (pin "D5") (pinfunction "(CM4_EVENTOUT/LCD_SEG29/TRACED0)PD9_D5") (pintype "bidirectional"))
    )
    (net (code "68") (name "PD10") (class "Default")
      (node (ref "J3") (pin "5") (pinfunction "5_5") (pintype "passive"))
      (node (ref "U2") (pin "E4") (pinfunction "(CM4_EVENTOUT/LCD_SEG30/TSC_G6_IO1/TRIG_INOUT)PD10_E4") (pintype "bidirectional"))
    )
    (net (code "69") (name "PD11") (class "Default")
      (node (ref "J3") (pin "1") (pinfunction "1_1") (pintype "passive"))
      (node (ref "U2") (pin "E5") (pinfunction "(CM4_EVENTOUT/LCD_SEG31/TSC_G6_IO2/LPTIM2_ETR)PD11_E5") (pintype "bidirectional"))
    )
    (net (code "70") (name "PD12") (class "Default")
      (node (ref "J6") (pin "4") (pinfunction "4_4") (pintype "passive"))
      (node (ref "U2") (pin "B8") (pinfunction "(CM4_EVENTOUT/LCD_SEG32/TSC_G6_IO3/LPTIM2_IN1)PD12_B8") (pintype "bidirectional"))
    )
    (net (code "71") (name "PD13") (class "Default")
      (node (ref "J6") (pin "6") (pinfunction "6_6") (pintype "passive"))
      (node (ref "U2") (pin "C9") (pinfunction "(CM4_EVENTOUT/LCD_SEG33/TSC_G6_IO4/LPTIM2_OUT)PD13_C9") (pintype "bidirectional"))
    )
    (net (code "72") (name "PD14") (class "Default")
      (node (ref "J7") (pin "5") (pinfunction "5_5") (pintype "passive"))
      (node (ref "U2") (pin "D8") (pinfunction "(CM4_EVENTOUT/LCD_SEG34/TIM1_CH1)PD14_D8") (pintype "bidirectional"))
    )
    (net (code "73") (name "PD15") (class "Default")
      (node (ref "J5") (pin "5") (pinfunction "5_5") (pintype "passive"))
      (node (ref "U2") (pin "E7") (pinfunction "(CM4_EVENTOUT/LCD_SEG35/TIM1_CH2)PD15_E7") (pintype "bidirectional"))
    )
    (net (code "74") (name "PE0") (class "Default")
      (node (ref "J6") (pin "5") (pinfunction "5_5") (pintype "passive"))
      (node (ref "U2") (pin "C8") (pinfunction "(CM4_EVENTOUT/LCD_SEG36/TSC_G7_IO3/TIM1_ETR/TIM16_CH1)PE0_C8") (pintype "bidirectional"))
    )
    (net (code "75") (name "PE1") (class "Default")
      (node (ref "J8") (pin "4") (pinfunction "4_4") (pintype "passive"))
      (node (ref "U2") (pin "B10") (pinfunction "(CM4_EVENTOUT/LCD_SEG37/TSC_G7_IO2/TIM17_CH1)PE1_B10") (pintype "bidirectional"))
    )
    (net (code "76") (name "PE2") (class "Default")
      (node (ref "J11") (pin "4") (pinfunction "4_4") (pintype "passive"))
      (node (ref "U2") (pin "E6") (pinfunction "(CM4_EVENTOUT/LCD_SEG38/TSC_G7_IO1/SAI1_MCLK_A/SAI1_PDM_CK1/TRACECK)PE2_E6") (pintype "bidirectional"))
    )
    (net (code "77") (name "PE3") (class "Default")
      (node (ref "J1") (pin "8") (pinfunction "8_8") (pintype "passive"))
      (node (ref "U2") (pin "G2") (pinfunction "(CM4_EVENTOUT)PE3_G2") (pintype "bidirectional"))
    )
    (net (code "78") (name "PE4") (class "Default")
      (node (ref "J1") (pin "9") (pinfunction "9_9") (pintype "passive"))
      (node (ref "U2") (pin "G1") (pinfunction "(CM4_EVENTOUT)PE4_G1") (pintype "bidirectional"))
    )
    (net (code "79") (name "PH0") (class "Default")
      (node (ref "J7") (pin "6") (pinfunction "6_6") (pintype "passive"))
      (node (ref "U2") (pin "E10") (pinfunction "(CM4_EVENTOUT)PH0_E10") (pintype "bidirectional"))
    )
    (net (code "80") (name "PH1") (class "Default")
      (node (ref "J9") (pin "4") (pinfunction "4_4") (pintype "passive"))
      (node (ref "U2") (pin "E9") (pinfunction "(CM4_EVENTOUT)PH1_E9") (pintype "bidirectional"))
    )
    (net (code "81") (name "VBAT") (class "Default")
      (node (ref "C32") (pin "1") (pinfunction "1_1") (pintype "passive"))
      (node (ref "J2") (pin "9") (pinfunction "9_9") (pintype "passive"))
      (node (ref "U2") (pin "C10") (pinfunction "VBAT_C10") (pintype "power_in"))
    )
    (net (code "82") (name "VCC") (class "Default")
      (node (ref "C18") (pin "1") (pinfunction "1_1") (pintype "passive"))
      (node (ref "C19") (pin "1") (pinfunction "1_1") (pintype "passive"))
      (node (ref "C20") (pin "1") (pinfunction "1_1") (pintype "passive"))
      (node (ref "C21") (pin "1") (pinfunction "1_1") (pintype "passive"))
      (node (ref "C22") (pin "1") (pinfunction "1_1") (pintype "passive"))
      (node (ref "C23") (pin "1") (pinfunction "1_1") (pintype "passive"))
      (node (ref "C24") (pin "1") (pinfunction "1_1") (pintype "passive"))
      (node (ref "C26") (pin "1") (pinfunction "1_1") (pintype "passive"))
      (node (ref "C29") (pin "1") (pinfunction "1_1") (pintype "passive"))
      (node (ref "C30") (pin "1") (pinfunction "1_1") (pintype "passive"))
      (node (ref "C31") (pin "1") (pinfunction "1_1") (pintype "passive"))
      (node (ref "J2") (pin "10") (pinfunction "10_10") (pintype "passive"))
      (node (ref "LED1") (pin "A") (pinfunction "A_A") (pintype "passive"))
      (node (ref "U2") (pin "A10") (pinfunction "VDD_A10") (pintype "power_in"))
      (node (ref "U2") (pin "B1") (pinfunction "VDD_B1") (pintype "power_in"))
      (node (ref "U2") (pin "B3") (pinfunction "VDDUSB_B3") (pintype "power_in"))
      (node (ref "U2") (pin "D1") (pinfunction "V_DD_SMPS_D1") (pintype "power_in"))
      (node (ref "U2") (pin "H8") (pinfunction "VREF+(VREFBUF_OUT)_H8") (pintype "power_in"))
      (node (ref "U2") (pin "H9") (pinfunction "VDDA_H9") (pintype "power_in"))
      (node (ref "U2") (pin "J10") (pinfunction "VDD_J10") (pintype "power_in"))
      (node (ref "U2") (pin "J3") (pinfunction "VDDRF_J3") (pintype "power_in"))
      (node (ref "U2") (pin "K5") (pinfunction "VDD_K5") (pintype "power_in"))
    )
    (net (code "83") (name "unconnected-(U2-(CM4_EVENTOUT{slash}EXT_PA_TX{slash}COMP1_OUT**)PB0-PadH2)") (class "Default")
      (node (ref "U2") (pin "H2") (pinfunction "(CM4_EVENTOUT/EXT_PA_TX/COMP1_OUT**)PB0_H2") (pintype "bidirectional"))
    )
    (net (code "84") (name "unconnected-(U2-(CM4_EVENTOUT{slash}LPUART1_RTS_DE{slash}LPTIM2_IN1**)PB1-PadH1)") (class "Default")
      (node (ref "U2") (pin "H1") (pinfunction "(CM4_EVENTOUT/LPUART1_RTS_DE/LPTIM2_IN1**)PB1_H1") (pintype "bidirectional"))
    )
  )
)
